# USB.net
KiCad netlist of a schematic drawn in Altium Designer
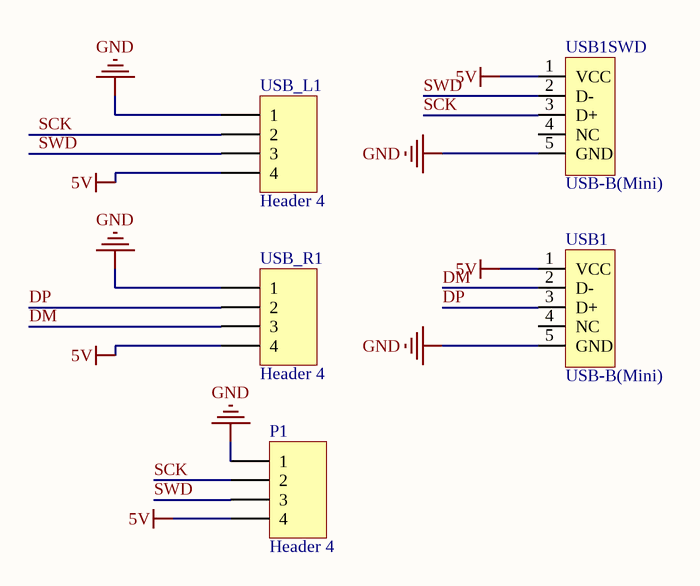
[diagram p0: 模型USB.SchDoc]

(export (version "E")
  (design (tool "Eeschema 10.0.6"))
  (components
    (comp (ref "P1")
      (value "Header 4")
      (footprint "HDR1X4")
      (description "Header, 4-Pin")
      (fields (field (name "PUBLISHER") "Altium Limited"))
      (libsource (lib "Miscellaneous Connectors") (part "Header 4"))
    )
    (comp (ref "USB1")
      (value "USB-B(Mini)")
      (footprint "USB/SM0.8-6H5_M")
      (libsource (lib "EXPLORER") (part "USB5"))
    )
    (comp (ref "USB1SWD")
      (value "USB-B(Mini)")
      (footprint "USB/SM0.8-6H5_M")
      (libsource (lib "EXPLORER") (part "USB5"))
    )
    (comp (ref "USB_L1")
      (value "Header 4")
      (footprint "SH1.0-4P")
      (description "Header, 4-Pin")
      (fields (field (name "PUBLISHER") "Altium Limited"))
      (libsource (lib "Explorer STM32F407封装库") (part "Header 4"))
    )
    (comp (ref "USB_R1")
      (value "Header 4")
      (footprint "SH1.0-4P")
      (description "Header, 4-Pin")
      (fields (field (name "PUBLISHER") "Altium Limited"))
      (libsource (lib "Explorer STM32F407封装库") (part "Header 4"))
    )
  )
  (nets
    (net (code "1") (name "/DM") (class "Default")
      (node (ref "USB1") (pin "2") (pinfunction "D-_2") (pintype "passive"))
      (node (ref "USB_R1") (pin "3") (pinfunction "3_3") (pintype "passive"))
    )
    (net (code "2") (name "/DP") (class "Default")
      (node (ref "USB1") (pin "3") (pinfunction "D+_3") (pintype "passive"))
      (node (ref "USB_R1") (pin "2") (pinfunction "2_2") (pintype "passive"))
    )
    (net (code "3") (name "/SCK") (class "Default")
      (node (ref "P1") (pin "2") (pinfunction "2_2") (pintype "passive"))
      (node (ref "USB1SWD") (pin "3") (pinfunction "D+_3") (pintype "passive"))
      (node (ref "USB_L1") (pin "2") (pinfunction "2_2") (pintype "passive"))
    )
    (net (code "4") (name "/SWD") (class "Default")
      (node (ref "P1") (pin "3") (pinfunction "3_3") (pintype "passive"))
      (node (ref "USB1SWD") (pin "2") (pinfunction "D-_2") (pintype "passive"))
      (node (ref "USB_L1") (pin "3") (pinfunction "3_3") (pintype "passive"))
    )
    (net (code "5") (name "5V") (class "Default")
      (node (ref "P1") (pin "4") (pinfunction "4_4") (pintype "passive"))
      (node (ref "USB1") (pin "1") (pinfunction "VCC_1") (pintype "passive"))
      (node (ref "USB1SWD") (pin "1") (pinfunction "VCC_1") (pintype "passive"))
      (node (ref "USB_L1") (pin "4") (pinfunction "4_4") (pintype "passive"))
      (node (ref "USB_R1") (pin "4") (pinfunction "4_4") (pintype "passive"))
    )
    (net (code "6") (name "GND") (class "Default")
      (node (ref "P1") (pin "1") (pinfunction "1_1") (pintype "passive"))
      (node (ref "USB1") (pin "5") (pinfunction "GND_5") (pintype "passive"))
      (node (ref "USB1SWD") (pin "5") (pinfunction "GND_5") (pintype "passive"))
      (node (ref "USB_L1") (pin "1") (pinfunction "1_1") (pintype "passive"))
      (node (ref "USB_R1") (pin "1") (pinfunction "1_1") (pintype "passive"))
    )
    (net (code "7") (name "unconnected-(USB1-NC-Pad4)") (class "Default")
      (node (ref "USB1") (pin "4") (pinfunction "NC_4") (pintype "passive"))
    )
    (net (code "8") (name "unconnected-(USB1SWD-NC-Pad4)") (class "Default")
      (node (ref "USB1SWD") (pin "4") (pinfunction "NC_4") (pintype "passive"))
    )
  )
)
